# seamonster_smd_draft1.net
KiCad netlist of a schematic drawn in EAGLE
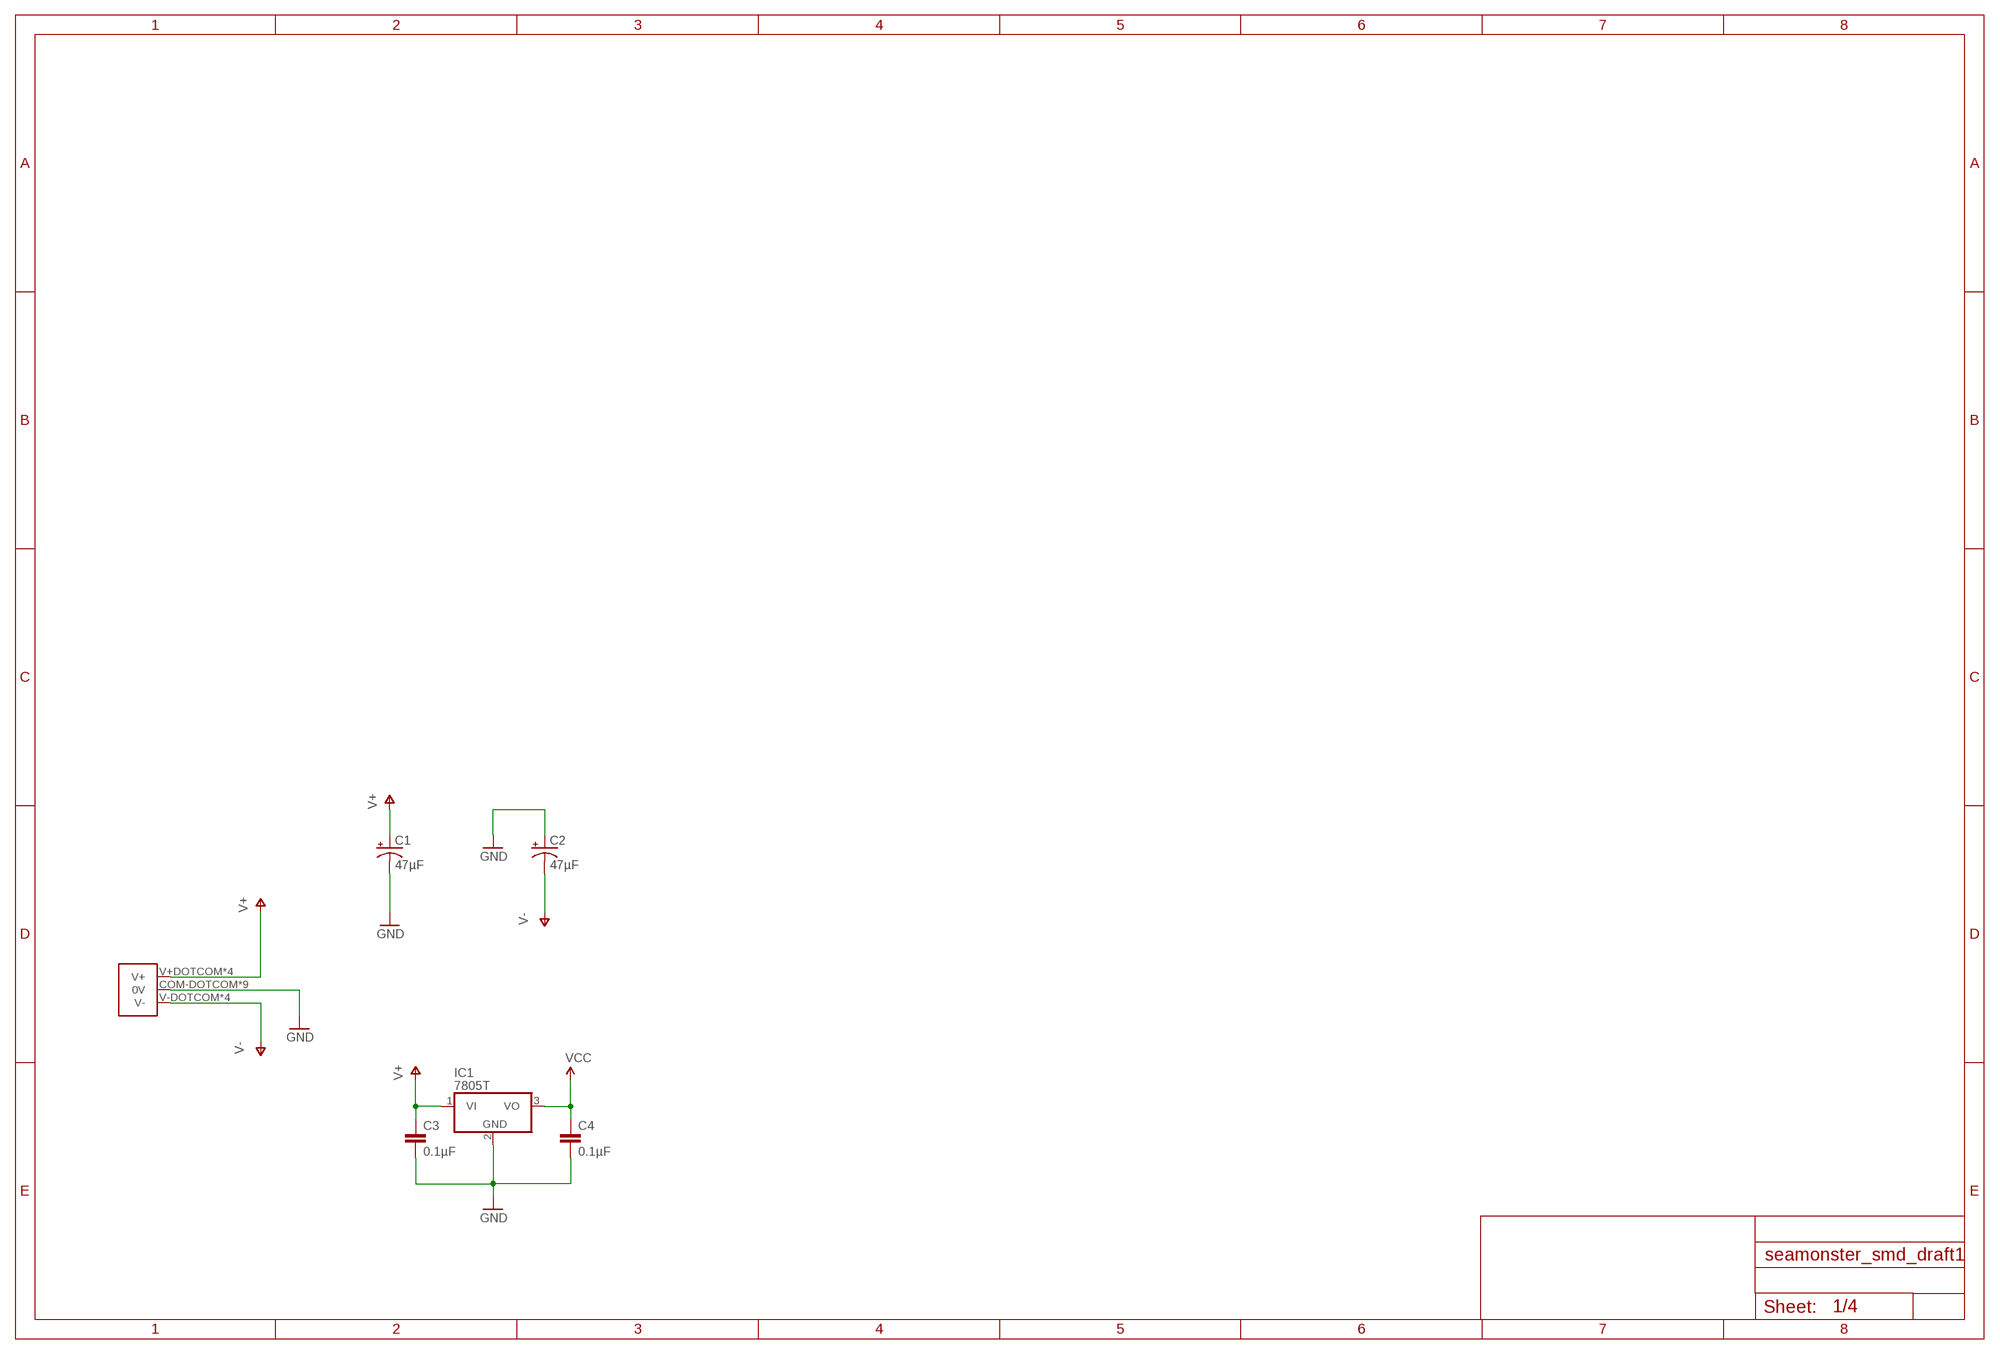
[diagram p0: schematic, sheet 1]
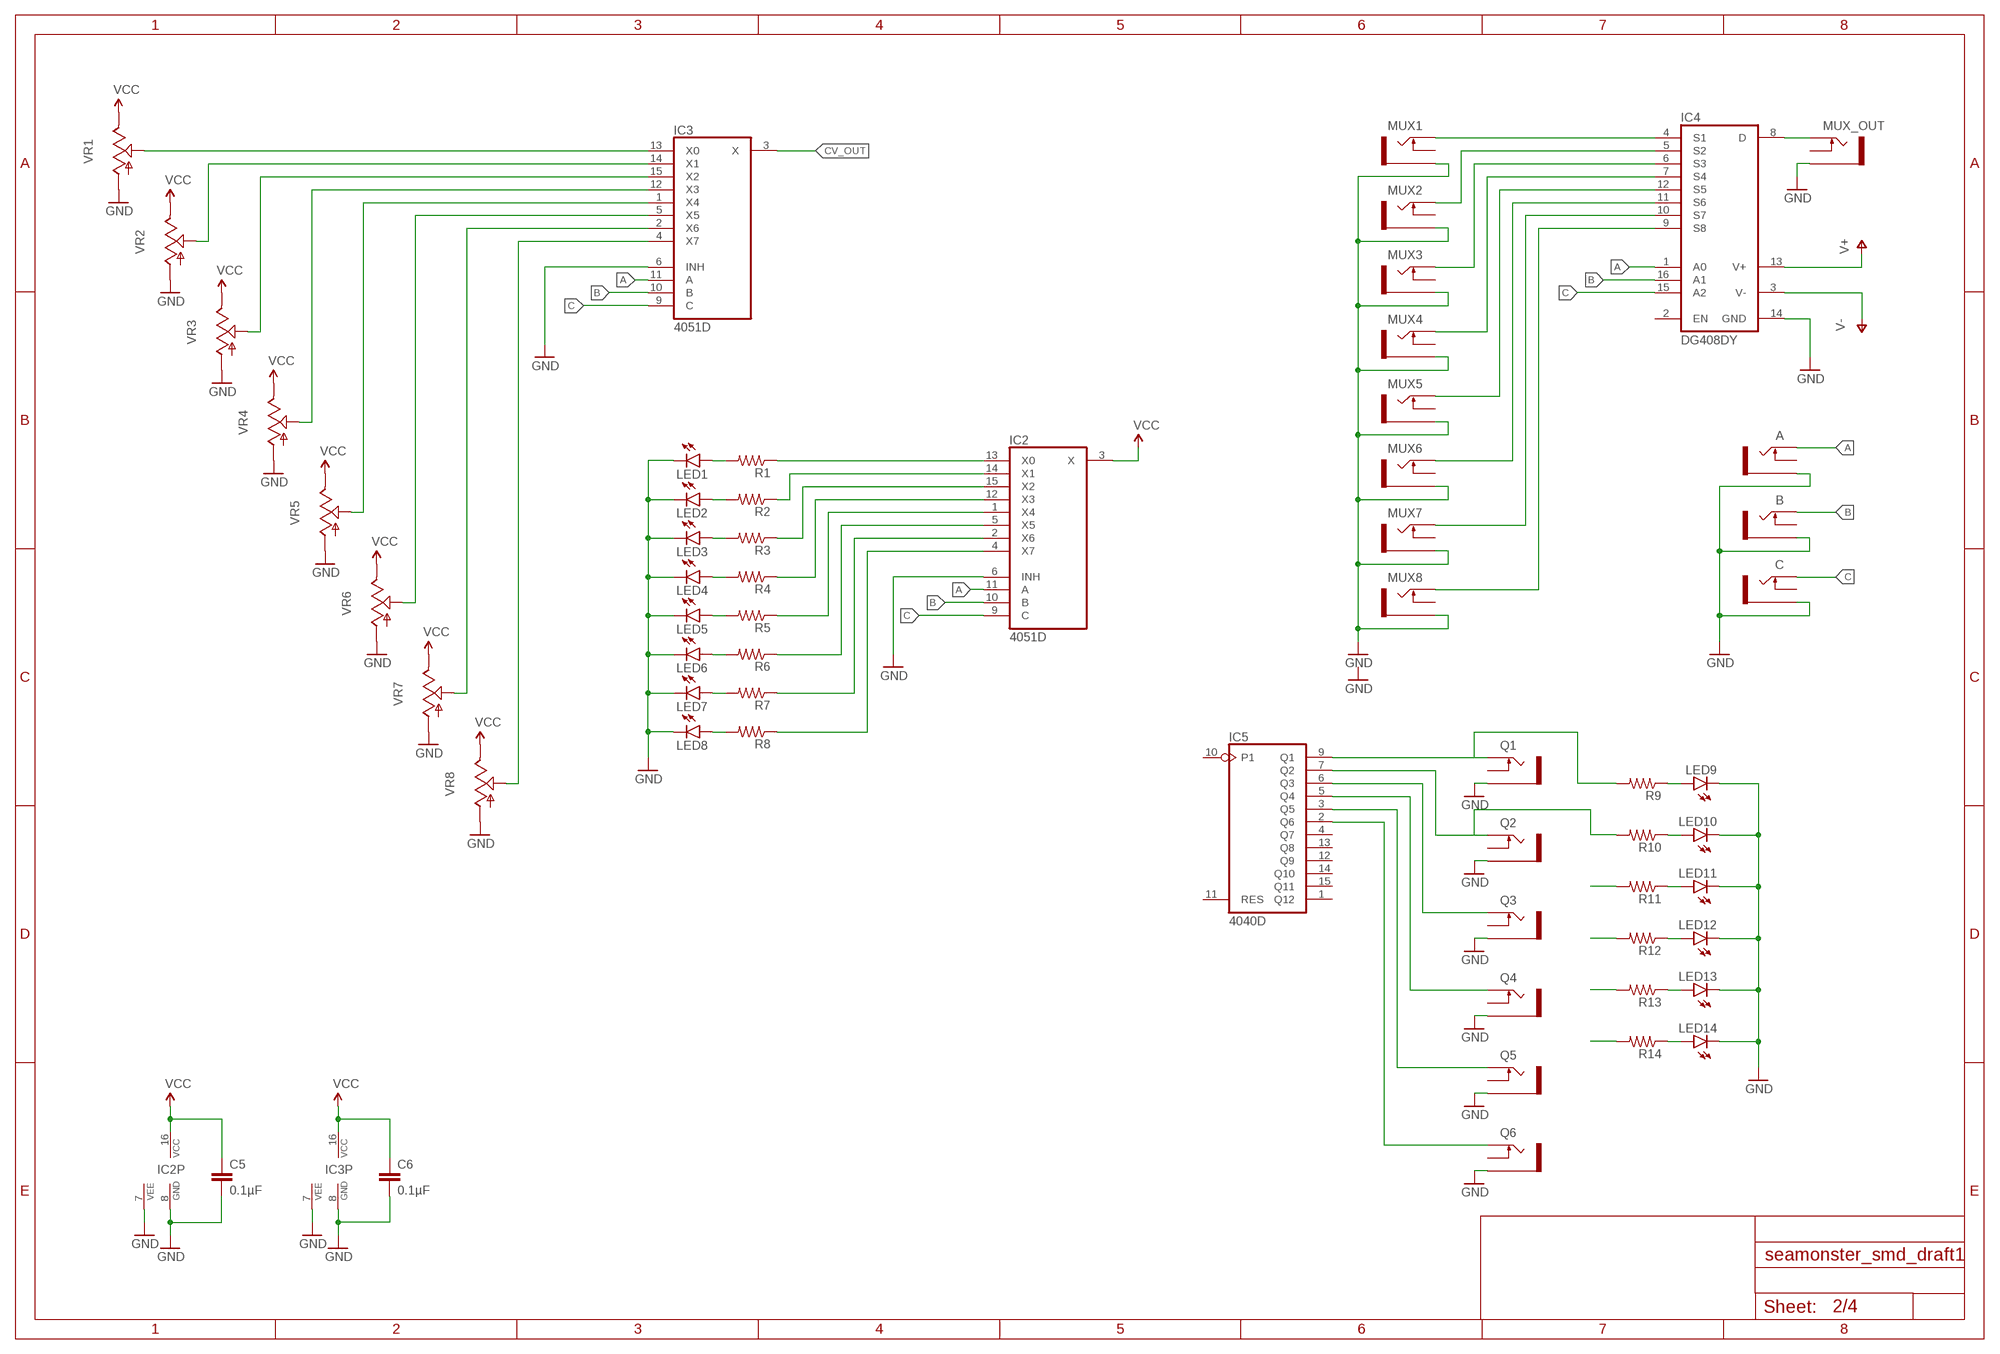
[diagram p1: schematic, sheet 2]
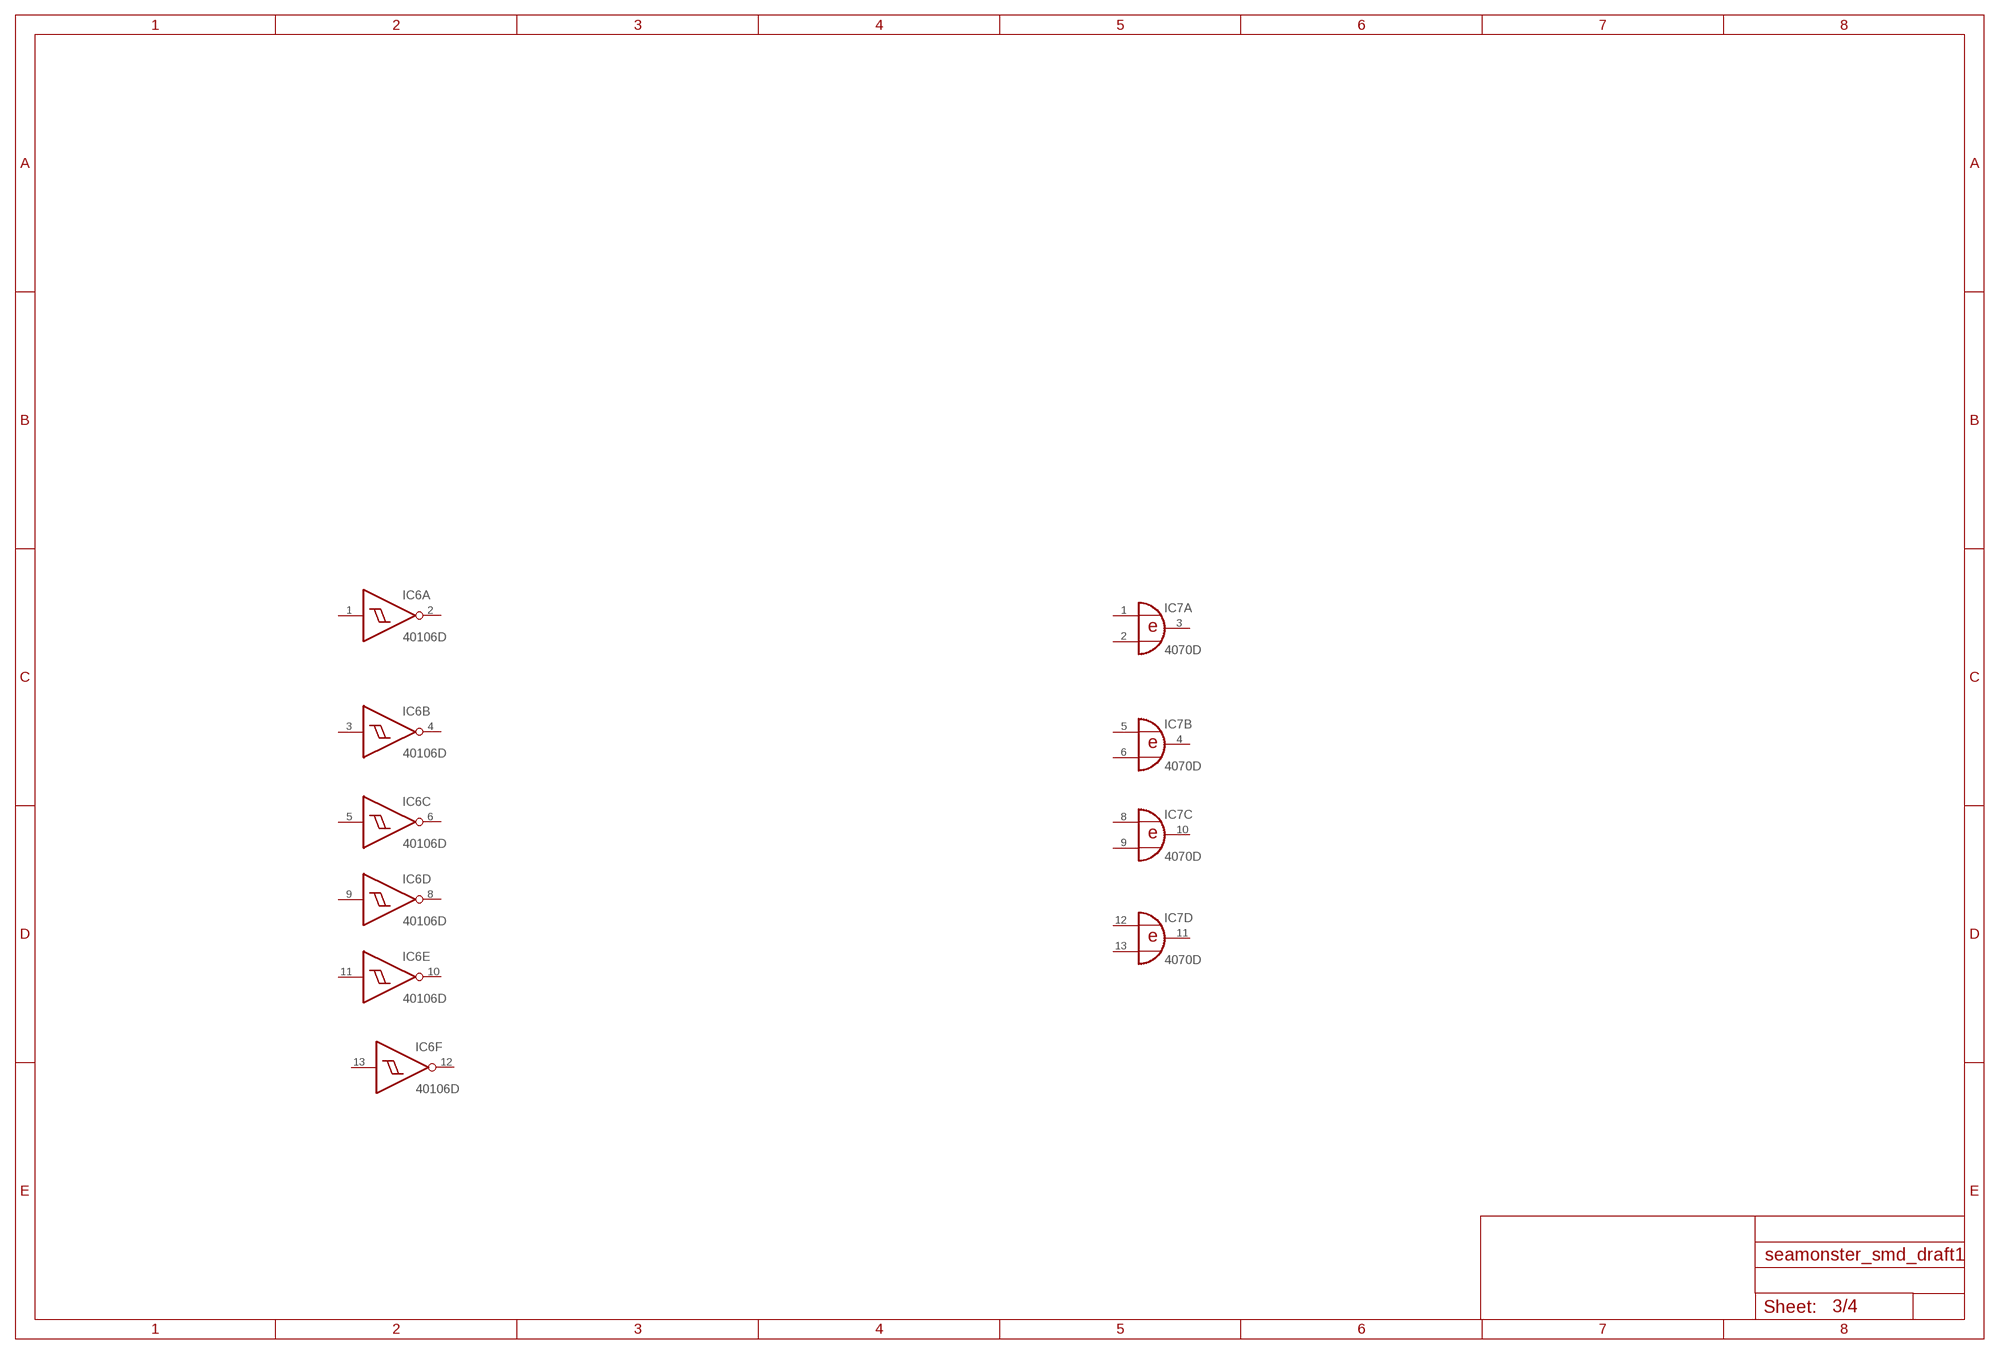
[diagram p2: schematic, sheet 3]
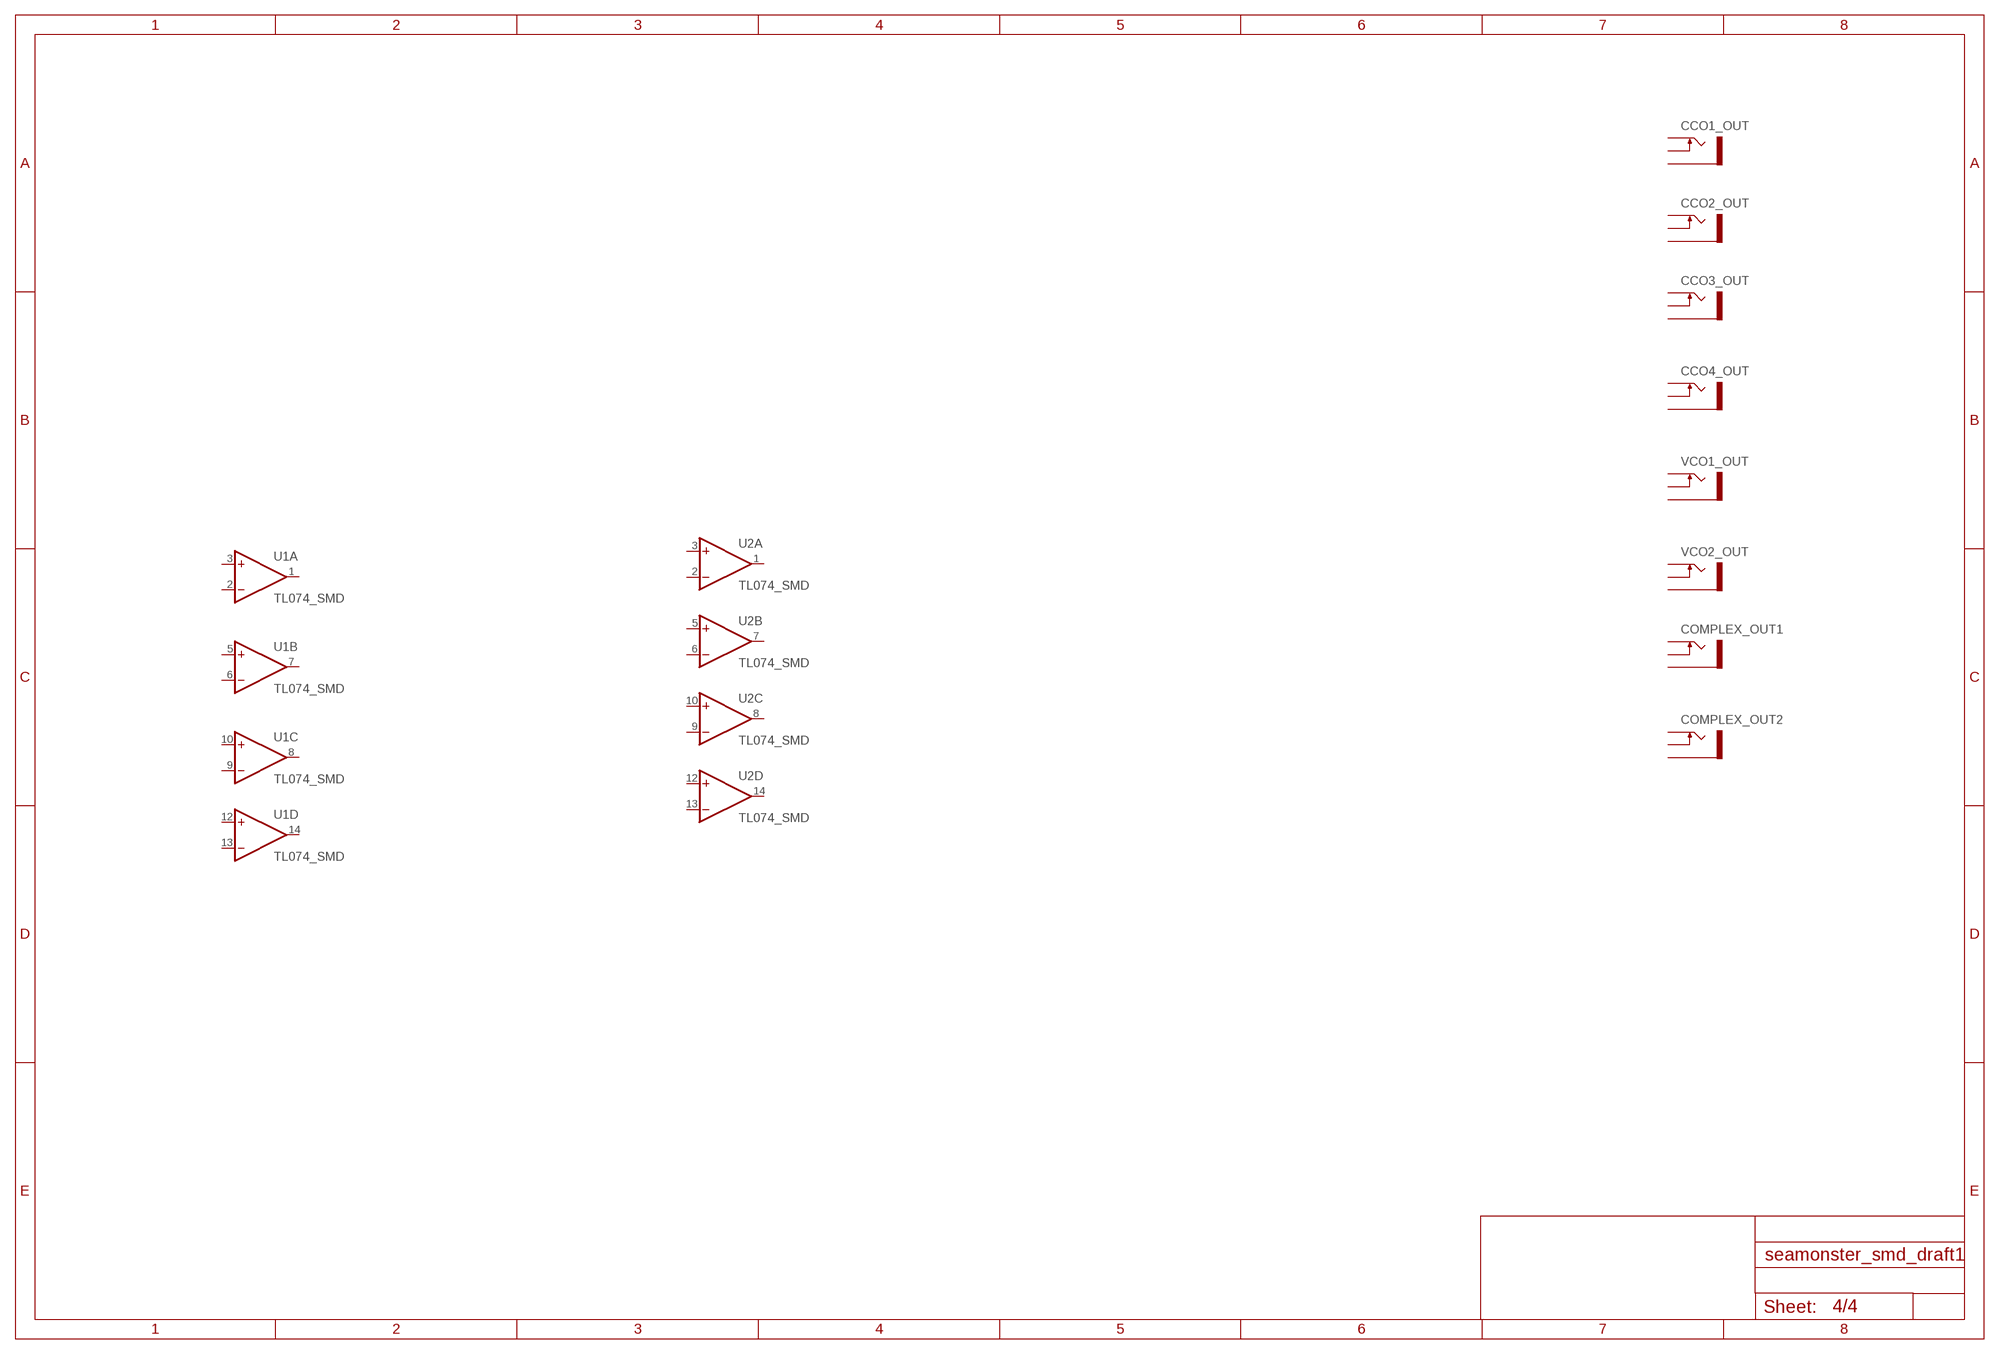
[diagram p3: schematic, sheet 4]

(export (version "E")
  (design (tool "Eeschema 10.0.6"))
  (components
    (comp (ref "IC6")
      (value "40106D")
      (footprint "eagle-import:SO14")
      (libsource (lib "eagle-import") (part "40106D"))
    )
    (comp (ref "IC7")
      (value "4070D")
      (footprint "eagle-import:SO14")
      (libsource (lib "eagle-import") (part "4070D"))
    )
    (comp (ref "CCO1_OUT")
      (value "THONKICONNNEW")
      (footprint "eagle-import:WQP-PJ301M-12_JACK")
      (libsource (lib "eagle-import") (part "THONKICONNNEW"))
    )
    (comp (ref "CCO2_OUT")
      (value "THONKICONNNEW")
      (footprint "eagle-import:WQP-PJ301M-12_JACK")
      (libsource (lib "eagle-import") (part "THONKICONNNEW"))
    )
    (comp (ref "CCO3_OUT")
      (value "THONKICONNNEW")
      (footprint "eagle-import:WQP-PJ301M-12_JACK")
      (libsource (lib "eagle-import") (part "THONKICONNNEW"))
    )
    (comp (ref "CCO4_OUT")
      (value "THONKICONNNEW")
      (footprint "eagle-import:WQP-PJ301M-12_JACK")
      (libsource (lib "eagle-import") (part "THONKICONNNEW"))
    )
    (comp (ref "COMPLEX_OUT1")
      (value "THONKICONNNEW")
      (footprint "eagle-import:WQP-PJ301M-12_JACK")
      (libsource (lib "eagle-import") (part "THONKICONNNEW"))
    )
    (comp (ref "COMPLEX_OUT2")
      (value "THONKICONNNEW")
      (footprint "eagle-import:WQP-PJ301M-12_JACK")
      (libsource (lib "eagle-import") (part "THONKICONNNEW"))
    )
    (comp (ref "U1")
      (value "TL074_SMD")
      (footprint "eagle-import:SO14")
      (libsource (lib "eagle-import") (part "TL074_SMD"))
    )
    (comp (ref "U2")
      (value "TL074_SMD")
      (footprint "eagle-import:SO14")
      (libsource (lib "eagle-import") (part "TL074_SMD"))
    )
    (comp (ref "VCO1_OUT")
      (value "THONKICONNNEW")
      (footprint "eagle-import:WQP-PJ301M-12_JACK")
      (libsource (lib "eagle-import") (part "THONKICONNNEW"))
    )
    (comp (ref "VCO2_OUT")
      (value "THONKICONNNEW")
      (footprint "eagle-import:WQP-PJ301M-12_JACK")
      (libsource (lib "eagle-import") (part "THONKICONNNEW"))
    )
    (comp (ref "A")
      (value "THONKICONNNEW")
      (footprint "eagle-import:WQP-PJ301M-12_JACK")
      (libsource (lib "eagle-import") (part "THONKICONNNEW"))
    )
    (comp (ref "B")
      (value "THONKICONNNEW")
      (footprint "eagle-import:WQP-PJ301M-12_JACK")
      (libsource (lib "eagle-import") (part "THONKICONNNEW"))
    )
    (comp (ref "C")
      (value "THONKICONNNEW")
      (footprint "eagle-import:WQP-PJ301M-12_JACK")
      (libsource (lib "eagle-import") (part "THONKICONNNEW"))
    )
    (comp (ref "C5")
      (value "0.1µF")
      (footprint "eagle-import:0805")
      (libsource (lib "eagle-import") (part "CAP0805"))
    )
    (comp (ref "C6")
      (value "0.1µF")
      (footprint "eagle-import:0805")
      (libsource (lib "eagle-import") (part "CAP0805"))
    )
    (comp (ref "IC2")
      (value "4051D")
      (footprint "eagle-import:SO16")
      (libsource (lib "eagle-import") (part "4051D"))
    )
    (comp (ref "IC3")
      (value "4051D")
      (footprint "eagle-import:SO16")
      (libsource (lib "eagle-import") (part "4051D"))
    )
    (comp (ref "IC4")
      (value "DG408DY")
      (footprint "eagle-import:SO16")
      (fields (field (name "MPN") "DG408DY+T"))
      (libsource (lib "eagle-import") (part "DG408DY"))
    )
    (comp (ref "IC5")
      (value "4040D")
      (footprint "eagle-import:SO16")
      (libsource (lib "eagle-import") (part "4040D"))
    )
    (comp (ref "LED1")
      (value "LED3MM")
      (footprint "eagle-import:LED3MM")
      (libsource (lib "eagle-import") (part "LED3MM"))
    )
    (comp (ref "LED2")
      (value "LED3MM")
      (footprint "eagle-import:LED3MM")
      (libsource (lib "eagle-import") (part "LED3MM"))
    )
    (comp (ref "LED3")
      (value "LED3MM")
      (footprint "eagle-import:LED3MM")
      (libsource (lib "eagle-import") (part "LED3MM"))
    )
    (comp (ref "LED4")
      (value "LED3MM")
      (footprint "eagle-import:LED3MM")
      (libsource (lib "eagle-import") (part "LED3MM"))
    )
    (comp (ref "LED5")
      (value "LED3MM")
      (footprint "eagle-import:LED3MM")
      (libsource (lib "eagle-import") (part "LED3MM"))
    )
    (comp (ref "LED6")
      (value "LED3MM")
      (footprint "eagle-import:LED3MM")
      (libsource (lib "eagle-import") (part "LED3MM"))
    )
    (comp (ref "LED7")
      (value "LED3MM")
      (footprint "eagle-import:LED3MM")
      (libsource (lib "eagle-import") (part "LED3MM"))
    )
    (comp (ref "LED8")
      (value "LED3MM")
      (footprint "eagle-import:LED3MM")
      (libsource (lib "eagle-import") (part "LED3MM"))
    )
    (comp (ref "LED9")
      (value "LED3MM")
      (footprint "eagle-import:LED3MM")
      (libsource (lib "eagle-import") (part "LED3MM"))
    )
    (comp (ref "LED10")
      (value "LED3MM")
      (footprint "eagle-import:LED3MM")
      (libsource (lib "eagle-import") (part "LED3MM"))
    )
    (comp (ref "LED11")
      (value "LED3MM")
      (footprint "eagle-import:LED3MM")
      (libsource (lib "eagle-import") (part "LED3MM"))
    )
    (comp (ref "LED12")
      (value "LED3MM")
      (footprint "eagle-import:LED3MM")
      (libsource (lib "eagle-import") (part "LED3MM"))
    )
    (comp (ref "LED13")
      (value "LED3MM")
      (footprint "eagle-import:LED3MM")
      (libsource (lib "eagle-import") (part "LED3MM"))
    )
    (comp (ref "LED14")
      (value "LED3MM")
      (footprint "eagle-import:LED3MM")
      (libsource (lib "eagle-import") (part "LED3MM"))
    )
    (comp (ref "MUX1")
      (value "THONKICONNNEW")
      (footprint "eagle-import:WQP-PJ301M-12_JACK")
      (libsource (lib "eagle-import") (part "THONKICONNNEW"))
    )
    (comp (ref "MUX2")
      (value "THONKICONNNEW")
      (footprint "eagle-import:WQP-PJ301M-12_JACK")
      (libsource (lib "eagle-import") (part "THONKICONNNEW"))
    )
    (comp (ref "MUX3")
      (value "THONKICONNNEW")
      (footprint "eagle-import:WQP-PJ301M-12_JACK")
      (libsource (lib "eagle-import") (part "THONKICONNNEW"))
    )
    (comp (ref "MUX4")
      (value "THONKICONNNEW")
      (footprint "eagle-import:WQP-PJ301M-12_JACK")
      (libsource (lib "eagle-import") (part "THONKICONNNEW"))
    )
    (comp (ref "MUX5")
      (value "THONKICONNNEW")
      (footprint "eagle-import:WQP-PJ301M-12_JACK")
      (libsource (lib "eagle-import") (part "THONKICONNNEW"))
    )
    (comp (ref "MUX6")
      (value "THONKICONNNEW")
      (footprint "eagle-import:WQP-PJ301M-12_JACK")
      (libsource (lib "eagle-import") (part "THONKICONNNEW"))
    )
    (comp (ref "MUX7")
      (value "THONKICONNNEW")
      (footprint "eagle-import:WQP-PJ301M-12_JACK")
      (libsource (lib "eagle-import") (part "THONKICONNNEW"))
    )
    (comp (ref "MUX8")
      (value "THONKICONNNEW")
      (footprint "eagle-import:WQP-PJ301M-12_JACK")
      (libsource (lib "eagle-import") (part "THONKICONNNEW"))
    )
    (comp (ref "MUX_OUT")
      (value "THONKICONNNEW")
      (footprint "eagle-import:WQP-PJ301M-12_JACK")
      (libsource (lib "eagle-import") (part "THONKICONNNEW"))
    )
    (comp (ref "Q1")
      (value "THONKICONNNEW")
      (footprint "eagle-import:WQP-PJ301M-12_JACK")
      (libsource (lib "eagle-import") (part "THONKICONNNEW"))
    )
    (comp (ref "Q2")
      (value "THONKICONNNEW")
      (footprint "eagle-import:WQP-PJ301M-12_JACK")
      (libsource (lib "eagle-import") (part "THONKICONNNEW"))
    )
    (comp (ref "Q3")
      (value "THONKICONNNEW")
      (footprint "eagle-import:WQP-PJ301M-12_JACK")
      (libsource (lib "eagle-import") (part "THONKICONNNEW"))
    )
    (comp (ref "Q4")
      (value "THONKICONNNEW")
      (footprint "eagle-import:WQP-PJ301M-12_JACK")
      (libsource (lib "eagle-import") (part "THONKICONNNEW"))
    )
    (comp (ref "Q5")
      (value "THONKICONNNEW")
      (footprint "eagle-import:WQP-PJ301M-12_JACK")
      (libsource (lib "eagle-import") (part "THONKICONNNEW"))
    )
    (comp (ref "Q6")
      (value "THONKICONNNEW")
      (footprint "eagle-import:WQP-PJ301M-12_JACK")
      (libsource (lib "eagle-import") (part "THONKICONNNEW"))
    )
    (comp (ref "R1")
      (value "RESISTOR0805-RES")
      (footprint "eagle-import:0805")
      (libsource (lib "eagle-import") (part "RESISTOR0805-RES"))
    )
    (comp (ref "R2")
      (value "RESISTOR0805-RES")
      (footprint "eagle-import:0805")
      (libsource (lib "eagle-import") (part "RESISTOR0805-RES"))
    )
    (comp (ref "R3")
      (value "RESISTOR0805-RES")
      (footprint "eagle-import:0805")
      (libsource (lib "eagle-import") (part "RESISTOR0805-RES"))
    )
    (comp (ref "R4")
      (value "RESISTOR0805-RES")
      (footprint "eagle-import:0805")
      (libsource (lib "eagle-import") (part "RESISTOR0805-RES"))
    )
    (comp (ref "R5")
      (value "RESISTOR0805-RES")
      (footprint "eagle-import:0805")
      (libsource (lib "eagle-import") (part "RESISTOR0805-RES"))
    )
    (comp (ref "R6")
      (value "RESISTOR0805-RES")
      (footprint "eagle-import:0805")
      (libsource (lib "eagle-import") (part "RESISTOR0805-RES"))
    )
    (comp (ref "R7")
      (value "RESISTOR0805-RES")
      (footprint "eagle-import:0805")
      (libsource (lib "eagle-import") (part "RESISTOR0805-RES"))
    )
    (comp (ref "R8")
      (value "RESISTOR0805-RES")
      (footprint "eagle-import:0805")
      (libsource (lib "eagle-import") (part "RESISTOR0805-RES"))
    )
    (comp (ref "R9")
      (value "RESISTOR0805-RES")
      (footprint "eagle-import:0805")
      (libsource (lib "eagle-import") (part "RESISTOR0805-RES"))
    )
    (comp (ref "R10")
      (value "RESISTOR0805-RES")
      (footprint "eagle-import:0805")
      (libsource (lib "eagle-import") (part "RESISTOR0805-RES"))
    )
    (comp (ref "R11")
      (value "RESISTOR0805-RES")
      (footprint "eagle-import:0805")
      (libsource (lib "eagle-import") (part "RESISTOR0805-RES"))
    )
    (comp (ref "R12")
      (value "RESISTOR0805-RES")
      (footprint "eagle-import:0805")
      (libsource (lib "eagle-import") (part "RESISTOR0805-RES"))
    )
    (comp (ref "R13")
      (value "RESISTOR0805-RES")
      (footprint "eagle-import:0805")
      (libsource (lib "eagle-import") (part "RESISTOR0805-RES"))
    )
    (comp (ref "R14")
      (value "RESISTOR0805-RES")
      (footprint "eagle-import:0805")
      (libsource (lib "eagle-import") (part "RESISTOR0805-RES"))
    )
    (comp (ref "VR1")
      (value "9MM_SNAP-IN_POT_")
      (footprint "eagle-import:9MM_SNAP-IN_POT")
      (libsource (lib "eagle-import") (part "9MM_SNAP-IN_POT_"))
    )
    (comp (ref "VR2")
      (value "9MM_SNAP-IN_POT_")
      (footprint "eagle-import:9MM_SNAP-IN_POT")
      (libsource (lib "eagle-import") (part "9MM_SNAP-IN_POT_"))
    )
    (comp (ref "VR3")
      (value "9MM_SNAP-IN_POT_")
      (footprint "eagle-import:9MM_SNAP-IN_POT")
      (libsource (lib "eagle-import") (part "9MM_SNAP-IN_POT_"))
    )
    (comp (ref "VR4")
      (value "9MM_SNAP-IN_POT_")
      (footprint "eagle-import:9MM_SNAP-IN_POT")
      (libsource (lib "eagle-import") (part "9MM_SNAP-IN_POT_"))
    )
    (comp (ref "VR5")
      (value "9MM_SNAP-IN_POT_")
      (footprint "eagle-import:9MM_SNAP-IN_POT")
      (libsource (lib "eagle-import") (part "9MM_SNAP-IN_POT_"))
    )
    (comp (ref "VR6")
      (value "9MM_SNAP-IN_POT_")
      (footprint "eagle-import:9MM_SNAP-IN_POT")
      (libsource (lib "eagle-import") (part "9MM_SNAP-IN_POT_"))
    )
    (comp (ref "VR7")
      (value "9MM_SNAP-IN_POT_")
      (footprint "eagle-import:9MM_SNAP-IN_POT")
      (libsource (lib "eagle-import") (part "9MM_SNAP-IN_POT_"))
    )
    (comp (ref "VR8")
      (value "9MM_SNAP-IN_POT_")
      (footprint "eagle-import:9MM_SNAP-IN_POT")
      (libsource (lib "eagle-import") (part "9MM_SNAP-IN_POT_"))
    )
    (comp (ref "C1")
      (value "47µF")
      (footprint "eagle-import:CPOL-RADIAL-10UF-25V")
      (libsource (lib "eagle-import") (part "CAP_POLPTH2"))
    )
    (comp (ref "C2")
      (value "47µF")
      (footprint "eagle-import:CPOL-RADIAL-10UF-25V")
      (libsource (lib "eagle-import") (part "CAP_POLPTH2"))
    )
    (comp (ref "C3")
      (value "0.1µF")
      (footprint "eagle-import:0805")
      (libsource (lib "eagle-import") (part "CAP0805"))
    )
    (comp (ref "C4")
      (value "0.1µF")
      (footprint "eagle-import:0805")
      (libsource (lib "eagle-import") (part "CAP0805"))
    )
    (comp (ref "IC1")
      (value "7805T")
      (footprint "eagle-import:TO220H")
      (libsource (lib "eagle-import") (part "78T05"))
    )
    (comp (ref "U$1")
      (value "COMBO_POWER")
      (footprint "eagle-import:COMBO_POWER")
      (libsource (lib "eagle-import") (part "COMBO_POWER"))
    )
  )
  (nets
    (net (code "1") (name "A") (class "Default")
      (node (ref "A") (pin "P$1_TIP") (pinfunction "TIP_P$1_TIP") (pintype "passive"))
      (node (ref "IC2") (pin "11") (pinfunction "A_11") (pintype "input"))
      (node (ref "IC3") (pin "11") (pinfunction "A_11") (pintype "input"))
      (node (ref "IC4") (pin "1") (pinfunction "A0_1") (pintype "input"))
    )
    (net (code "2") (name "B") (class "Default")
      (node (ref "B") (pin "P$1_TIP") (pinfunction "TIP_P$1_TIP") (pintype "passive"))
      (node (ref "IC2") (pin "10") (pinfunction "B_10") (pintype "input"))
      (node (ref "IC3") (pin "10") (pinfunction "B_10") (pintype "input"))
      (node (ref "IC4") (pin "16") (pinfunction "A1_16") (pintype "input"))
    )
    (net (code "3") (name "C") (class "Default")
      (node (ref "C") (pin "P$1_TIP") (pinfunction "TIP_P$1_TIP") (pintype "passive"))
      (node (ref "IC2") (pin "9") (pinfunction "C_9") (pintype "input"))
      (node (ref "IC3") (pin "9") (pinfunction "C_9") (pintype "input"))
      (node (ref "IC4") (pin "15") (pinfunction "A2_15") (pintype "input"))
    )
    (net (code "4") (name "CV_OUT") (class "Default")
      (node (ref "IC3") (pin "3") (pinfunction "X_3") (pintype "bidirectional"))
    )
    (net (code "5") (name "GND") (class "Default")
      (node (ref "A") (pin "P$3_SLEEVE") (pinfunction "SLEEVE_P$3_SLEEVE") (pintype "passive"))
      (node (ref "B") (pin "P$3_SLEEVE") (pinfunction "SLEEVE_P$3_SLEEVE") (pintype "passive"))
      (node (ref "C") (pin "P$3_SLEEVE") (pinfunction "SLEEVE_P$3_SLEEVE") (pintype "passive"))
      (node (ref "C1") (pin "2") (pinfunction "-_2") (pintype "passive"))
      (node (ref "C2") (pin "1") (pinfunction "+_1") (pintype "passive"))
      (node (ref "C3") (pin "2") (pinfunction "2_2") (pintype "passive"))
      (node (ref "C4") (pin "2") (pinfunction "2_2") (pintype "passive"))
      (node (ref "C5") (pin "2") (pinfunction "2_2") (pintype "passive"))
      (node (ref "C6") (pin "2") (pinfunction "2_2") (pintype "passive"))
      (node (ref "IC1") (pin "2") (pinfunction "GND_2") (pintype "passive"))
      (node (ref "IC2") (pin "6") (pinfunction "INH_6") (pintype "input"))
      (node (ref "IC2") (pin "7") (pinfunction "VEE_7") (pintype "power_in"))
      (node (ref "IC2") (pin "8") (pinfunction "GND_8") (pintype "power_in"))
      (node (ref "IC3") (pin "6") (pinfunction "INH_6") (pintype "input"))
      (node (ref "IC3") (pin "7") (pinfunction "VEE_7") (pintype "power_in"))
      (node (ref "IC3") (pin "8") (pinfunction "GND_8") (pintype "power_in"))
      (node (ref "IC4") (pin "14") (pinfunction "GND_14") (pintype "power_in"))
      (node (ref "LED1") (pin "K") (pinfunction "C_K") (pintype "passive"))
      (node (ref "LED10") (pin "K") (pinfunction "C_K") (pintype "passive"))
      (node (ref "LED11") (pin "K") (pinfunction "C_K") (pintype "passive"))
      (node (ref "LED12") (pin "K") (pinfunction "C_K") (pintype "passive"))
      (node (ref "LED13") (pin "K") (pinfunction "C_K") (pintype "passive"))
      (node (ref "LED14") (pin "K") (pinfunction "C_K") (pintype "passive"))
      (node (ref "LED2") (pin "K") (pinfunction "C_K") (pintype "passive"))
      (node (ref "LED3") (pin "K") (pinfunction "C_K") (pintype "passive"))
      (node (ref "LED4") (pin "K") (pinfunction "C_K") (pintype "passive"))
      (node (ref "LED5") (pin "K") (pinfunction "C_K") (pintype "passive"))
      (node (ref "LED6") (pin "K") (pinfunction "C_K") (pintype "passive"))
      (node (ref "LED7") (pin "K") (pinfunction "C_K") (pintype "passive"))
      (node (ref "LED8") (pin "K") (pinfunction "C_K") (pintype "passive"))
      (node (ref "LED9") (pin "K") (pinfunction "C_K") (pintype "passive"))
      (node (ref "MUX1") (pin "P$3_SLEEVE") (pinfunction "SLEEVE_P$3_SLEEVE") (pintype "passive"))
      (node (ref "MUX2") (pin "P$3_SLEEVE") (pinfunction "SLEEVE_P$3_SLEEVE") (pintype "passive"))
      (node (ref "MUX3") (pin "P$3_SLEEVE") (pinfunction "SLEEVE_P$3_SLEEVE") (pintype "passive"))
      (node (ref "MUX4") (pin "P$3_SLEEVE") (pinfunction "SLEEVE_P$3_SLEEVE") (pintype "passive"))
      (node (ref "MUX5") (pin "P$3_SLEEVE") (pinfunction "SLEEVE_P$3_SLEEVE") (pintype "passive"))
      (node (ref "MUX6") (pin "P$3_SLEEVE") (pinfunction "SLEEVE_P$3_SLEEVE") (pintype "passive"))
      (node (ref "MUX7") (pin "P$3_SLEEVE") (pinfunction "SLEEVE_P$3_SLEEVE") (pintype "passive"))
      (node (ref "MUX8") (pin "P$3_SLEEVE") (pinfunction "SLEEVE_P$3_SLEEVE") (pintype "passive"))
      (node (ref "MUX_OUT") (pin "P$3_SLEEVE") (pinfunction "SLEEVE_P$3_SLEEVE") (pintype "passive"))
      (node (ref "Q1") (pin "P$3_SLEEVE") (pinfunction "SLEEVE_P$3_SLEEVE") (pintype "passive"))
      (node (ref "Q2") (pin "P$3_SLEEVE") (pinfunction "SLEEVE_P$3_SLEEVE") (pintype "passive"))
      (node (ref "Q3") (pin "P$3_SLEEVE") (pinfunction "SLEEVE_P$3_SLEEVE") (pintype "passive"))
      (node (ref "Q4") (pin "P$3_SLEEVE") (pinfunction "SLEEVE_P$3_SLEEVE") (pintype "passive"))
      (node (ref "Q5") (pin "P$3_SLEEVE") (pinfunction "SLEEVE_P$3_SLEEVE") (pintype "passive"))
      (node (ref "Q6") (pin "P$3_SLEEVE") (pinfunction "SLEEVE_P$3_SLEEVE") (pintype "passive"))
      (node (ref "U$1") (pin "COM-DOTCOM") (pinfunction "0V_COM-DOTCOM") (pintype "bidirectional"))
      (node (ref "U$1") (pin "COM-EURO1") (pinfunction "0V_COM-EURO1") (pintype "bidirectional"))
      (node (ref "U$1") (pin "COM-EURO2") (pinfunction "0V_COM-EURO2") (pintype "bidirectional"))
      (node (ref "U$1") (pin "COM-EURO3") (pinfunction "0V_COM-EURO3") (pintype "bidirectional"))
      (node (ref "U$1") (pin "COM-EURO4") (pinfunction "0V_COM-EURO4") (pintype "bidirectional"))
      (node (ref "U$1") (pin "COM-EURO5") (pinfunction "0V_COM-EURO5") (pintype "bidirectional"))
      (node (ref "U$1") (pin "COM-EURO6") (pinfunction "0V_COM-EURO6") (pintype "bidirectional"))
      (node (ref "U$1") (pin "COM-MOTM1") (pinfunction "0V_COM-MOTM1") (pintype "bidirectional"))
      (node (ref "U$1") (pin "COM_MOTM2") (pinfunction "0V_COM_MOTM2") (pintype "bidirectional"))
      (node (ref "VR1") (pin "1") (pinfunction "A_1") (pintype "passive"))
      (node (ref "VR2") (pin "1") (pinfunction "A_1") (pintype "passive"))
      (node (ref "VR3") (pin "1") (pinfunction "A_1") (pintype "passive"))
      (node (ref "VR4") (pin "1") (pinfunction "A_1") (pintype "passive"))
      (node (ref "VR5") (pin "1") (pinfunction "A_1") (pintype "passive"))
      (node (ref "VR6") (pin "1") (pinfunction "A_1") (pintype "passive"))
      (node (ref "VR7") (pin "1") (pinfunction "A_1") (pintype "passive"))
      (node (ref "VR8") (pin "1") (pinfunction "A_1") (pintype "passive"))
    )
    (net (code "6") (name "Net-(IC2A-X0)") (class "Default")
      (node (ref "IC2") (pin "13") (pinfunction "X0_13") (pintype "bidirectional"))
      (node (ref "R1") (pin "1") (pinfunction "1_1") (pintype "passive"))
    )
    (net (code "7") (name "Net-(IC2A-X1)") (class "Default")
      (node (ref "IC2") (pin "14") (pinfunction "X1_14") (pintype "bidirectional"))
      (node (ref "R2") (pin "1") (pinfunction "1_1") (pintype "passive"))
    )
    (net (code "8") (name "Net-(IC2A-X2)") (class "Default")
      (node (ref "IC2") (pin "15") (pinfunction "X2_15") (pintype "bidirectional"))
      (node (ref "R3") (pin "1") (pinfunction "1_1") (pintype "passive"))
    )
    (net (code "9") (name "Net-(IC2A-X3)") (class "Default")
      (node (ref "IC2") (pin "12") (pinfunction "X3_12") (pintype "bidirectional"))
      (node (ref "R4") (pin "1") (pinfunction "1_1") (pintype "passive"))
    )
    (net (code "10") (name "Net-(IC2A-X4)") (class "Default")
      (node (ref "IC2") (pin "1") (pinfunction "X4_1") (pintype "bidirectional"))
      (node (ref "R5") (pin "1") (pinfunction "1_1") (pintype "passive"))
    )
    (net (code "11") (name "Net-(IC2A-X5)") (class "Default")
      (node (ref "IC2") (pin "5") (pinfunction "X5_5") (pintype "bidirectional"))
      (node (ref "R6") (pin "1") (pinfunction "1_1") (pintype "passive"))
    )
    (net (code "12") (name "Net-(IC2A-X6)") (class "Default")
      (node (ref "IC2") (pin "2") (pinfunction "X6_2") (pintype "bidirectional"))
      (node (ref "R7") (pin "1") (pinfunction "1_1") (pintype "passive"))
    )
    (net (code "13") (name "Net-(IC2A-X7)") (class "Default")
      (node (ref "IC2") (pin "4") (pinfunction "X7_4") (pintype "bidirectional"))
      (node (ref "R8") (pin "1") (pinfunction "1_1") (pintype "passive"))
    )
    (net (code "14") (name "Net-(IC3A-X0)") (class "Default")
      (node (ref "IC3") (pin "13") (pinfunction "X0_13") (pintype "bidirectional"))
      (node (ref "VR1") (pin "2") (pinfunction "S_2") (pintype "passive"))
    )
    (net (code "15") (name "Net-(IC3A-X1)") (class "Default")
      (node (ref "IC3") (pin "14") (pinfunction "X1_14") (pintype "bidirectional"))
      (node (ref "VR2") (pin "2") (pinfunction "S_2") (pintype "passive"))
    )
    (net (code "16") (name "Net-(IC3A-X2)") (class "Default")
      (node (ref "IC3") (pin "15") (pinfunction "X2_15") (pintype "bidirectional"))
      (node (ref "VR3") (pin "2") (pinfunction "S_2") (pintype "passive"))
    )
    (net (code "17") (name "Net-(IC3A-X3)") (class "Default")
      (node (ref "IC3") (pin "12") (pinfunction "X3_12") (pintype "bidirectional"))
      (node (ref "VR4") (pin "2") (pinfunction "S_2") (pintype "passive"))
    )
    (net (code "18") (name "Net-(IC3A-X4)") (class "Default")
      (node (ref "IC3") (pin "1") (pinfunction "X4_1") (pintype "bidirectional"))
      (node (ref "VR5") (pin "2") (pinfunction "S_2") (pintype "passive"))
    )
    (net (code "19") (name "Net-(IC3A-X5)") (class "Default")
      (node (ref "IC3") (pin "5") (pinfunction "X5_5") (pintype "bidirectional"))
      (node (ref "VR6") (pin "2") (pinfunction "S_2") (pintype "passive"))
    )
    (net (code "20") (name "Net-(IC3A-X6)") (class "Default")
      (node (ref "IC3") (pin "2") (pinfunction "X6_2") (pintype "bidirectional"))
      (node (ref "VR7") (pin "2") (pinfunction "S_2") (pintype "passive"))
    )
    (net (code "21") (name "Net-(IC3A-X7)") (class "Default")
      (node (ref "IC3") (pin "4") (pinfunction "X7_4") (pintype "bidirectional"))
      (node (ref "VR8") (pin "2") (pinfunction "S_2") (pintype "passive"))
    )
    (net (code "22") (name "Net-(IC4-D)") (class "Default")
      (node (ref "IC4") (pin "8") (pinfunction "D_8") (pintype "passive"))
      (node (ref "MUX_OUT") (pin "P$1_TIP") (pinfunction "TIP_P$1_TIP") (pintype "passive"))
    )
    (net (code "23") (name "Net-(IC4-S1)") (class "Default")
      (node (ref "IC4") (pin "4") (pinfunction "S1_4") (pintype "passive"))
      (node (ref "MUX1") (pin "P$1_TIP") (pinfunction "TIP_P$1_TIP") (pintype "passive"))
    )
    (net (code "24") (name "Net-(IC4-S2)") (class "Default")
      (node (ref "IC4") (pin "5") (pinfunction "S2_5") (pintype "passive"))
      (node (ref "MUX2") (pin "P$1_TIP") (pinfunction "TIP_P$1_TIP") (pintype "passive"))
    )
    (net (code "25") (name "Net-(IC4-S3)") (class "Default")
      (node (ref "IC4") (pin "6") (pinfunction "S3_6") (pintype "passive"))
      (node (ref "MUX3") (pin "P$1_TIP") (pinfunction "TIP_P$1_TIP") (pintype "passive"))
    )
    (net (code "26") (name "Net-(IC4-S4)") (class "Default")
      (node (ref "IC4") (pin "7") (pinfunction "S4_7") (pintype "passive"))
      (node (ref "MUX4") (pin "P$1_TIP") (pinfunction "TIP_P$1_TIP") (pintype "passive"))
    )
    (net (code "27") (name "Net-(IC4-S5)") (class "Default")
      (node (ref "IC4") (pin "12") (pinfunction "S5_12") (pintype "passive"))
      (node (ref "MUX5") (pin "P$1_TIP") (pinfunction "TIP_P$1_TIP") (pintype "passive"))
    )
    (net (code "28") (name "Net-(IC4-S6)") (class "Default")
      (node (ref "IC4") (pin "11") (pinfunction "S6_11") (pintype "passive"))
      (node (ref "MUX6") (pin "P$1_TIP") (pinfunction "TIP_P$1_TIP") (pintype "passive"))
    )
    (net (code "29") (name "Net-(IC4-S7)") (class "Default")
      (node (ref "IC4") (pin "10") (pinfunction "S7_10") (pintype "passive"))
      (node (ref "MUX7") (pin "P$1_TIP") (pinfunction "TIP_P$1_TIP") (pintype "passive"))
    )
    (net (code "30") (name "Net-(IC4-S8)") (class "Default")
      (node (ref "IC4") (pin "9") (pinfunction "S8_9") (pintype "passive"))
      (node (ref "MUX8") (pin "P$1_TIP") (pinfunction "TIP_P$1_TIP") (pintype "passive"))
    )
    (net (code "31") (name "Net-(IC5A-Q1)") (class "Default")
      (node (ref "IC5") (pin "9") (pinfunction "Q1_9") (pintype "output"))
      (node (ref "Q1") (pin "P$1_TIP") (pinfunction "TIP_P$1_TIP") (pintype "passive"))
      (node (ref "R9") (pin "2") (pinfunction "2_2") (pintype "passive"))
    )
    (net (code "32") (name "Net-(IC5A-Q2)") (class "Default")
      (node (ref "IC5") (pin "7") (pinfunction "Q2_7") (pintype "output"))
      (node (ref "Q2") (pin "P$1_TIP") (pinfunction "TIP_P$1_TIP") (pintype "passive"))
      (node (ref "R10") (pin "2") (pinfunction "2_2") (pintype "passive"))
    )
    (net (code "33") (name "Net-(IC5A-Q3)") (class "Default")
      (node (ref "IC5") (pin "6") (pinfunction "Q3_6") (pintype "output"))
      (node (ref "Q3") (pin "P$1_TIP") (pinfunction "TIP_P$1_TIP") (pintype "passive"))
    )
    (net (code "34") (name "Net-(IC5A-Q4)") (class "Default")
      (node (ref "IC5") (pin "5") (pinfunction "Q4_5") (pintype "output"))
      (node (ref "Q4") (pin "P$1_TIP") (pinfunction "TIP_P$1_TIP") (pintype "passive"))
    )
    (net (code "35") (name "Net-(IC5A-Q5)") (class "Default")
      (node (ref "IC5") (pin "3") (pinfunction "Q5_3") (pintype "output"))
      (node (ref "Q5") (pin "P$1_TIP") (pinfunction "TIP_P$1_TIP") (pintype "passive"))
    )
    (net (code "36") (name "Net-(IC5A-Q6)") (class "Default")
      (node (ref "IC5") (pin "2") (pinfunction "Q6_2") (pintype "output"))
      (node (ref "Q6") (pin "P$1_TIP") (pinfunction "TIP_P$1_TIP") (pintype "passive"))
    )
    (net (code "37") (name "Net-(LED1-PadA)") (class "Default")
      (node (ref "LED1") (pin "A") (pinfunction "A_A") (pintype "passive"))
      (node (ref "R1") (pin "2") (pinfunction "2_2") (pintype "passive"))
    )
    (net (code "38") (name "Net-(LED2-PadA)") (class "Default")
      (node (ref "LED2") (pin "A") (pinfunction "A_A") (pintype "passive"))
      (node (ref "R2") (pin "2") (pinfunction "2_2") (pintype "passive"))
    )
    (net (code "39") (name "Net-(LED3-PadA)") (class "Default")
      (node (ref "LED3") (pin "A") (pinfunction "A_A") (pintype "passive"))
      (node (ref "R3") (pin "2") (pinfunction "2_2") (pintype "passive"))
    )
    (net (code "40") (name "Net-(LED4-PadA)") (class "Default")
      (node (ref "LED4") (pin "A") (pinfunction "A_A") (pintype "passive"))
      (node (ref "R4") (pin "2") (pinfunction "2_2") (pintype "passive"))
    )
    (net (code "41") (name "Net-(LED5-PadA)") (class "Default")
      (node (ref "LED5") (pin "A") (pinfunction "A_A") (pintype "passive"))
      (node (ref "R5") (pin "2") (pinfunction "2_2") (pintype "passive"))
    )
    (net (code "42") (name "Net-(LED6-PadA)") (class "Default")
      (node (ref "LED6") (pin "A") (pinfunction "A_A") (pintype "passive"))
      (node (ref "R6") (pin "2") (pinfunction "2_2") (pintype "passive"))
    )
    (net (code "43") (name "Net-(LED7-PadA)") (class "Default")
      (node (ref "LED7") (pin "A") (pinfunction "A_A") (pintype "passive"))
      (node (ref "R7") (pin "2") (pinfunction "2_2") (pintype "passive"))
    )
    (net (code "44") (name "Net-(LED8-PadA)") (class "Default")
      (node (ref "LED8") (pin "A") (pinfunction "A_A") (pintype "passive"))
      (node (ref "R8") (pin "2") (pinfunction "2_2") (pintype "passive"))
    )
    (net (code "45") (name "Net-(LED9-PadA)") (class "Default")
      (node (ref "LED9") (pin "A") (pinfunction "A_A") (pintype "passive"))
      (node (ref "R9") (pin "1") (pinfunction "1_1") (pintype "passive"))
    )
    (net (code "46") (name "Net-(LED10-PadA)") (class "Default")
      (node (ref "LED10") (pin "A") (pinfunction "A_A") (pintype "passive"))
      (node (ref "R10") (pin "1") (pinfunction "1_1") (pintype "passive"))
    )
    (net (code "47") (name "Net-(LED11-PadA)") (class "Default")
      (node (ref "LED11") (pin "A") (pinfunction "A_A") (pintype "passive"))
      (node (ref "R11") (pin "1") (pinfunction "1_1") (pintype "passive"))
    )
    (net (code "48") (name "Net-(LED12-PadA)") (class "Default")
      (node (ref "LED12") (pin "A") (pinfunction "A_A") (pintype "passive"))
      (node (ref "R12") (pin "1") (pinfunction "1_1") (pintype "passive"))
    )
    (net (code "49") (name "Net-(LED13-PadA)") (class "Default")
      (node (ref "LED13") (pin "A") (pinfunction "A_A") (pintype "passive"))
      (node (ref "R13") (pin "1") (pinfunction "1_1") (pintype "passive"))
    )
    (net (code "50") (name "Net-(LED14-PadA)") (class "Default")
      (node (ref "LED14") (pin "A") (pinfunction "A_A") (pintype "passive"))
      (node (ref "R14") (pin "1") (pinfunction "1_1") (pintype "passive"))
    )
    (net (code "51") (name "V+") (class "Default")
      (node (ref "C1") (pin "1") (pinfunction "+_1") (pintype "passive"))
      (node (ref "C3") (pin "1") (pinfunction "1_1") (pintype "passive"))
      (node (ref "IC1") (pin "1") (pinfunction "VI_1") (pintype "input"))
      (node (ref "IC4") (pin "13") (pinfunction "V+_13") (pintype "power_in"))
      (node (ref "U$1") (pin "V+DOTCOM") (pinfunction "V+_V+DOTCOM") (pintype "bidirectional"))
      (node (ref "U$1") (pin "V+EURO1") (pinfunction "V+_V+EURO1") (pintype "bidirectional"))
      (node (ref "U$1") (pin "V+EURO2") (pinfunction "V+_V+EURO2") (pintype "bidirectional"))
      (node (ref "U$1") (pin "V+MOTM") (pinfunction "V+_V+MOTM") (pintype "bidirectional"))
    )
    (net (code "52") (name "V-") (class "Default")
      (node (ref "C2") (pin "2") (pinfunction "-_2") (pintype "passive"))
      (node (ref "IC4") (pin "3") (pinfunction "V-_3") (pintype "power_in"))
      (node (ref "U$1") (pin "V-DOTCOM") (pinfunction "V-_V-DOTCOM") (pintype "bidirectional"))
      (node (ref "U$1") (pin "V-EURO1") (pinfunction "V-_V-EURO1") (pintype "bidirectional"))
      (node (ref "U$1") (pin "V-EURO2") (pinfunction "V-_V-EURO2") (pintype "bidirectional"))
      (node (ref "U$1") (pin "V-MOTM") (pinfunction "V-_V-MOTM") (pintype "bidirectional"))
    )
    (net (code "53") (name "VCC") (class "Default")
      (node (ref "C4") (pin "1") (pinfunction "1_1") (pintype "passive"))
      (node (ref "C5") (pin "1") (pinfunction "1_1") (pintype "passive"))
      (node (ref "C6") (pin "1") (pinfunction "1_1") (pintype "passive"))
      (node (ref "IC1") (pin "3") (pinfunction "VO_3") (pintype "passive"))
      (node (ref "IC2") (pin "16") (pinfunction "VCC_16") (pintype "power_in"))
      (node (ref "IC2") (pin "3") (pinfunction "X_3") (pintype "bidirectional"))
      (node (ref "IC3") (pin "16") (pinfunction "VCC_16") (pintype "power_in"))
      (node (ref "VR1") (pin "3") (pinfunction "E_3") (pintype "passive"))
      (node (ref "VR2") (pin "3") (pinfunction "E_3") (pintype "passive"))
      (node (ref "VR3") (pin "3") (pinfunction "E_3") (pintype "passive"))
      (node (ref "VR4") (pin "3") (pinfunction "E_3") (pintype "passive"))
      (node (ref "VR5") (pin "3") (pinfunction "E_3") (pintype "passive"))
      (node (ref "VR6") (pin "3") (pinfunction "E_3") (pintype "passive"))
      (node (ref "VR7") (pin "3") (pinfunction "E_3") (pintype "passive"))
      (node (ref "VR8") (pin "3") (pinfunction "E_3") (pintype "passive"))
    )
    (net (code "54") (name "unconnected-(A-SWITCH-PadP$2_SWITCH)") (class "Default")
      (node (ref "A") (pin "P$2_SWITCH") (pinfunction "SWITCH_P$2_SWITCH") (pintype "passive"))
    )
    (net (code "55") (name "unconnected-(B-SWITCH-PadP$2_SWITCH)") (class "Default")
      (node (ref "B") (pin "P$2_SWITCH") (pinfunction "SWITCH_P$2_SWITCH") (pintype "passive"))
    )
    (net (code "56") (name "unconnected-(C-SWITCH-PadP$2_SWITCH)") (class "Default")
      (node (ref "C") (pin "P$2_SWITCH") (pinfunction "SWITCH_P$2_SWITCH") (pintype "passive"))
    )
    (net (code "57") (name "unconnected-(CCO1_OUT-SLEEVE-PadP$3_SLEEVE)") (class "Default")
      (node (ref "CCO1_OUT") (pin "P$3_SLEEVE") (pinfunction "SLEEVE_P$3_SLEEVE") (pintype "passive"))
    )
    (net (code "58") (name "unconnected-(CCO1_OUT-SWITCH-PadP$2_SWITCH)") (class "Default")
      (node (ref "CCO1_OUT") (pin "P$2_SWITCH") (pinfunction "SWITCH_P$2_SWITCH") (pintype "passive"))
    )
    (net (code "59") (name "unconnected-(CCO1_OUT-TIP-PadP$1_TIP)") (class "Default")
      (node (ref "CCO1_OUT") (pin "P$1_TIP") (pinfunction "TIP_P$1_TIP") (pintype "passive"))
    )
    (net (code "60") (name "unconnected-(CCO2_OUT-SLEEVE-PadP$3_SLEEVE)") (class "Default")
      (node (ref "CCO2_OUT") (pin "P$3_SLEEVE") (pinfunction "SLEEVE_P$3_SLEEVE") (pintype "passive"))
    )
    (net (code "61") (name "unconnected-(CCO2_OUT-SWITCH-PadP$2_SWITCH)") (class "Default")
      (node (ref "CCO2_OUT") (pin "P$2_SWITCH") (pinfunction "SWITCH_P$2_SWITCH") (pintype "passive"))
    )
    (net (code "62") (name "unconnected-(CCO2_OUT-TIP-PadP$1_TIP)") (class "Default")
      (node (ref "CCO2_OUT") (pin "P$1_TIP") (pinfunction "TIP_P$1_TIP") (pintype "passive"))
    )
    (net (code "63") (name "unconnected-(CCO3_OUT-SLEEVE-PadP$3_SLEEVE)") (class "Default")
      (node (ref "CCO3_OUT") (pin "P$3_SLEEVE") (pinfunction "SLEEVE_P$3_SLEEVE") (pintype "passive"))
    )
    (net (code "64") (name "unconnected-(CCO3_OUT-SWITCH-PadP$2_SWITCH)") (class "Default")
      (node (ref "CCO3_OUT") (pin "P$2_SWITCH") (pinfunction "SWITCH_P$2_SWITCH") (pintype "passive"))
    )
    (net (code "65") (name "unconnected-(CCO3_OUT-TIP-PadP$1_TIP)") (class "Default")
      (node (ref "CCO3_OUT") (pin "P$1_TIP") (pinfunction "TIP_P$1_TIP") (pintype "passive"))
    )
    (net (code "66") (name "unconnected-(CCO4_OUT-SLEEVE-PadP$3_SLEEVE)") (class "Default")
      (node (ref "CCO4_OUT") (pin "P$3_SLEEVE") (pinfunction "SLEEVE_P$3_SLEEVE") (pintype "passive"))
    )
    (net (code "67") (name "unconnected-(CCO4_OUT-SWITCH-PadP$2_SWITCH)") (class "Default")
      (node (ref "CCO4_OUT") (pin "P$2_SWITCH") (pinfunction "SWITCH_P$2_SWITCH") (pintype "passive"))
    )
    (net (code "68") (name "unconnected-(CCO4_OUT-TIP-PadP$1_TIP)") (class "Default")
      (node (ref "CCO4_OUT") (pin "P$1_TIP") (pinfunction "TIP_P$1_TIP") (pintype "passive"))
    )
    (net (code "69") (name "unconnected-(COMPLEX_OUT1-SLEEVE-PadP$3_SLEEVE)") (class "Default")
      (node (ref "COMPLEX_OUT1") (pin "P$3_SLEEVE") (pinfunction "SLEEVE_P$3_SLEEVE") (pintype "passive"))
    )
    (net (code "70") (name "unconnected-(COMPLEX_OUT1-SWITCH-PadP$2_SWITCH)") (class "Default")
      (node (ref "COMPLEX_OUT1") (pin "P$2_SWITCH") (pinfunction "SWITCH_P$2_SWITCH") (pintype "passive"))
    )
    (net (code "71") (name "unconnected-(COMPLEX_OUT1-TIP-PadP$1_TIP)") (class "Default")
      (node (ref "COMPLEX_OUT1") (pin "P$1_TIP") (pinfunction "TIP_P$1_TIP") (pintype "passive"))
    )
    (net (code "72") (name "unconnected-(COMPLEX_OUT2-SLEEVE-PadP$3_SLEEVE)") (class "Default")
      (node (ref "COMPLEX_OUT2") (pin "P$3_SLEEVE") (pinfunction "SLEEVE_P$3_SLEEVE") (pintype "passive"))
    )
    (net (code "73") (name "unconnected-(COMPLEX_OUT2-SWITCH-PadP$2_SWITCH)") (class "Default")
      (node (ref "COMPLEX_OUT2") (pin "P$2_SWITCH") (pinfunction "SWITCH_P$2_SWITCH") (pintype "passive"))
    )
    (net (code "74") (name "unconnected-(COMPLEX_OUT2-TIP-PadP$1_TIP)") (class "Default")
      (node (ref "COMPLEX_OUT2") (pin "P$1_TIP") (pinfunction "TIP_P$1_TIP") (pintype "passive"))
    )
    (net (code "75") (name "unconnected-(IC4-EN-Pad2)") (class "Default")
      (node (ref "IC4") (pin "2") (pinfunction "EN_2") (pintype "input"))
    )
    (net (code "76") (name "unconnected-(IC5A-P1-Pad10)") (class "Default")
      (node (ref "IC5") (pin "10") (pinfunction "P1_10") (pintype "input"))
    )
    (net (code "77") (name "unconnected-(IC5A-Q7-Pad4)") (class "Default")
      (node (ref "IC5") (pin "4") (pinfunction "Q7_4") (pintype "output"))
    )
    (net (code "78") (name "unconnected-(IC5A-Q8-Pad13)") (class "Default")
      (node (ref "IC5") (pin "13") (pinfunction "Q8_13") (pintype "output"))
    )
    (net (code "79") (name "unconnected-(IC5A-Q9-Pad12)") (class "Default")
      (node (ref "IC5") (pin "12") (pinfunction "Q9_12") (pintype "output"))
    )
    (net (code "80") (name "unconnected-(IC5A-Q10-Pad14)") (class "Default")
      (node (ref "IC5") (pin "14") (pinfunction "Q10_14") (pintype "output"))
    )
    (net (code "81") (name "unconnected-(IC5A-Q11-Pad15)") (class "Default")
      (node (ref "IC5") (pin "15") (pinfunction "Q11_15") (pintype "output"))
    )
    (net (code "82") (name "unconnected-(IC5A-Q12-Pad1)") (class "Default")
      (node (ref "IC5") (pin "1") (pinfunction "Q12_1") (pintype "output"))
    )
    (net (code "83") (name "unconnected-(IC5A-RES-Pad11)") (class "Default")
      (node (ref "IC5") (pin "11") (pinfunction "RES_11") (pintype "input"))
    )
    (net (code "84") (name "unconnected-(IC6A-I-Pad1)") (class "Default")
      (node (ref "IC6") (pin "1") (pinfunction "I_1") (pintype "input"))
    )
    (net (code "85") (name "unconnected-(IC6A-O-Pad2)") (class "Default")
      (node (ref "IC6") (pin "2") (pinfunction "O_2") (pintype "output"))
    )
    (net (code "86") (name "unconnected-(IC6B-I-Pad3)") (class "Default")
      (node (ref "IC6") (pin "3") (pinfunction "I_3") (pintype "input"))
    )
    (net (code "87") (name "unconnected-(IC6B-O-Pad4)") (class "Default")
      (node (ref "IC6") (pin "4") (pinfunction "O_4") (pintype "output"))
    )
    (net (code "88") (name "unconnected-(IC6C-I-Pad5)") (class "Default")
      (node (ref "IC6") (pin "5") (pinfunction "I_5") (pintype "input"))
    )
    (net (code "89") (name "unconnected-(IC6C-O-Pad6)") (class "Default")
      (node (ref "IC6") (pin "6") (pinfunction "O_6") (pintype "output"))
    )
    (net (code "90") (name "unconnected-(IC6D-I-Pad9)") (class "Default")
      (node (ref "IC6") (pin "9") (pinfunction "I_9") (pintype "input"))
    )
    (net (code "91") (name "unconnected-(IC6D-O-Pad8)") (class "Default")
      (node (ref "IC6") (pin "8") (pinfunction "O_8") (pintype "output"))
    )
    (net (code "92") (name "unconnected-(IC6E-I-Pad11)") (class "Default")
      (node (ref "IC6") (pin "11") (pinfunction "I_11") (pintype "input"))
    )
    (net (code "93") (name "unconnected-(IC6E-O-Pad10)") (class "Default")
      (node (ref "IC6") (pin "10") (pinfunction "O_10") (pintype "output"))
    )
    (net (code "94") (name "unconnected-(IC6F-I-Pad13)") (class "Default")
      (node (ref "IC6") (pin "13") (pinfunction "I_13") (pintype "input"))
    )
    (net (code "95") (name "unconnected-(IC6F-O-Pad12)") (class "Default")
      (node (ref "IC6") (pin "12") (pinfunction "O_12") (pintype "output"))
    )
    (net (code "96") (name "unconnected-(IC7A-I0-Pad1)") (class "Default")
      (node (ref "IC7") (pin "1") (pinfunction "I0_1") (pintype "input"))
    )
    (net (code "97") (name "unconnected-(IC7A-I1-Pad2)") (class "Default")
      (node (ref "IC7") (pin "2") (pinfunction "I1_2") (pintype "input"))
    )
    (net (code "98") (name "unconnected-(IC7A-O-Pad3)") (class "Default")
      (node (ref "IC7") (pin "3") (pinfunction "O_3") (pintype "output"))
    )
    (net (code "99") (name "unconnected-(IC7B-I0-Pad5)") (class "Default")
      (node (ref "IC7") (pin "5") (pinfunction "I0_5") (pintype "input"))
    )
    (net (code "100") (name "unconnected-(IC7B-I1-Pad6)") (class "Default")
      (node (ref "IC7") (pin "6") (pinfunction "I1_6") (pintype "input"))
    )
    (net (code "101") (name "unconnected-(IC7B-O-Pad4)") (class "Default")
      (node (ref "IC7") (pin "4") (pinfunction "O_4") (pintype "output"))
    )
    (net (code "102") (name "unconnected-(IC7C-I0-Pad8)") (class "Default")
      (node (ref "IC7") (pin "8") (pinfunction "I0_8") (pintype "input"))
    )
    (net (code "103") (name "unconnected-(IC7C-I1-Pad9)") (class "Default")
      (node (ref "IC7") (pin "9") (pinfunction "I1_9") (pintype "input"))
    )
    (net (code "104") (name "unconnected-(IC7C-O-Pad10)") (class "Default")
      (node (ref "IC7") (pin "10") (pinfunction "O_10") (pintype "output"))
    )
    (net (code "105") (name "unconnected-(IC7D-I0-Pad12)") (class "Default")
      (node (ref "IC7") (pin "12") (pinfunction "I0_12") (pintype "input"))
    )
    (net (code "106") (name "unconnected-(IC7D-I1-Pad13)") (class "Default")
      (node (ref "IC7") (pin "13") (pinfunction "I1_13") (pintype "input"))
    )
    (net (code "107") (name "unconnected-(IC7D-O-Pad11)") (class "Default")
      (node (ref "IC7") (pin "11") (pinfunction "O_11") (pintype "output"))
    )
    (net (code "108") (name "unconnected-(MUX1-SWITCH-PadP$2_SWITCH)") (class "Default")
      (node (ref "MUX1") (pin "P$2_SWITCH") (pinfunction "SWITCH_P$2_SWITCH") (pintype "passive"))
    )
    (net (code "109") (name "unconnected-(MUX2-SWITCH-PadP$2_SWITCH)") (class "Default")
      (node (ref "MUX2") (pin "P$2_SWITCH") (pinfunction "SWITCH_P$2_SWITCH") (pintype "passive"))
    )
    (net (code "110") (name "unconnected-(MUX3-SWITCH-PadP$2_SWITCH)") (class "Default")
      (node (ref "MUX3") (pin "P$2_SWITCH") (pinfunction "SWITCH_P$2_SWITCH") (pintype "passive"))
    )
    (net (code "111") (name "unconnected-(MUX4-SWITCH-PadP$2_SWITCH)") (class "Default")
      (node (ref "MUX4") (pin "P$2_SWITCH") (pinfunction "SWITCH_P$2_SWITCH") (pintype "passive"))
    )
    (net (code "112") (name "unconnected-(MUX5-SWITCH-PadP$2_SWITCH)") (class "Default")
      (node (ref "MUX5") (pin "P$2_SWITCH") (pinfunction "SWITCH_P$2_SWITCH") (pintype "passive"))
    )
    (net (code "113") (name "unconnected-(MUX6-SWITCH-PadP$2_SWITCH)") (class "Default")
      (node (ref "MUX6") (pin "P$2_SWITCH") (pinfunction "SWITCH_P$2_SWITCH") (pintype "passive"))
    )
    (net (code "114") (name "unconnected-(MUX7-SWITCH-PadP$2_SWITCH)") (class "Default")
      (node (ref "MUX7") (pin "P$2_SWITCH") (pinfunction "SWITCH_P$2_SWITCH") (pintype "passive"))
    )
    (net (code "115") (name "unconnected-(MUX8-SWITCH-PadP$2_SWITCH)") (class "Default")
      (node (ref "MUX8") (pin "P$2_SWITCH") (pinfunction "SWITCH_P$2_SWITCH") (pintype "passive"))
    )
    (net (code "116") (name "unconnected-(MUX_OUT-SWITCH-PadP$2_SWITCH)") (class "Default")
      (node (ref "MUX_OUT") (pin "P$2_SWITCH") (pinfunction "SWITCH_P$2_SWITCH") (pintype "passive"))
    )
    (net (code "117") (name "unconnected-(Q1-SWITCH-PadP$2_SWITCH)") (class "Default")
      (node (ref "Q1") (pin "P$2_SWITCH") (pinfunction "SWITCH_P$2_SWITCH") (pintype "passive"))
    )
    (net (code "118") (name "unconnected-(Q2-SWITCH-PadP$2_SWITCH)") (class "Default")
      (node (ref "Q2") (pin "P$2_SWITCH") (pinfunction "SWITCH_P$2_SWITCH") (pintype "passive"))
    )
    (net (code "119") (name "unconnected-(Q3-SWITCH-PadP$2_SWITCH)") (class "Default")
      (node (ref "Q3") (pin "P$2_SWITCH") (pinfunction "SWITCH_P$2_SWITCH") (pintype "passive"))
    )
    (net (code "120") (name "unconnected-(Q4-SWITCH-PadP$2_SWITCH)") (class "Default")
      (node (ref "Q4") (pin "P$2_SWITCH") (pinfunction "SWITCH_P$2_SWITCH") (pintype "passive"))
    )
    (net (code "121") (name "unconnected-(Q5-SWITCH-PadP$2_SWITCH)") (class "Default")
      (node (ref "Q5") (pin "P$2_SWITCH") (pinfunction "SWITCH_P$2_SWITCH") (pintype "passive"))
    )
    (net (code "122") (name "unconnected-(Q6-SWITCH-PadP$2_SWITCH)") (class "Default")
      (node (ref "Q6") (pin "P$2_SWITCH") (pinfunction "SWITCH_P$2_SWITCH") (pintype "passive"))
    )
    (net (code "123") (name "unconnected-(R11-Pad2)") (class "Default")
      (node (ref "R11") (pin "2") (pinfunction "2_2") (pintype "passive"))
    )
    (net (code "124") (name "unconnected-(R12-Pad2)") (class "Default")
      (node (ref "R12") (pin "2") (pinfunction "2_2") (pintype "passive"))
    )
    (net (code "125") (name "unconnected-(R13-Pad2)") (class "Default")
      (node (ref "R13") (pin "2") (pinfunction "2_2") (pintype "passive"))
    )
    (net (code "126") (name "unconnected-(R14-Pad2)") (class "Default")
      (node (ref "R14") (pin "2") (pinfunction "2_2") (pintype "passive"))
    )
    (net (code "127") (name "unconnected-(U1A-+IN-Pad3)") (class "Default")
      (node (ref "U1") (pin "3") (pinfunction "+IN_3") (pintype "input"))
    )
    (net (code "128") (name "unconnected-(U1A--IN-Pad2)") (class "Default")
      (node (ref "U1") (pin "2") (pinfunction "-IN_2") (pintype "input"))
    )
    (net (code "129") (name "unconnected-(U1A-OUT-Pad1)") (class "Default")
      (node (ref "U1") (pin "1") (pinfunction "OUT_1") (pintype "output"))
    )
    (net (code "130") (name "unconnected-(U1B-+IN-Pad5)") (class "Default")
      (node (ref "U1") (pin "5") (pinfunction "+IN_5") (pintype "input"))
    )
    (net (code "131") (name "unconnected-(U1B--IN-Pad6)") (class "Default")
      (node (ref "U1") (pin "6") (pinfunction "-IN_6") (pintype "input"))
    )
    (net (code "132") (name "unconnected-(U1B-OUT-Pad7)") (class "Default")
      (node (ref "U1") (pin "7") (pinfunction "OUT_7") (pintype "output"))
    )
    (net (code "133") (name "unconnected-(U1C-+IN-Pad10)") (class "Default")
      (node (ref "U1") (pin "10") (pinfunction "+IN_10") (pintype "input"))
    )
    (net (code "134") (name "unconnected-(U1C--IN-Pad9)") (class "Default")
      (node (ref "U1") (pin "9") (pinfunction "-IN_9") (pintype "input"))
    )
    (net (code "135") (name "unconnected-(U1C-OUT-Pad8)") (class "Default")
      (node (ref "U1") (pin "8") (pinfunction "OUT_8") (pintype "output"))
    )
    (net (code "136") (name "unconnected-(U1D-+IN-Pad12)") (class "Default")
      (node (ref "U1") (pin "12") (pinfunction "+IN_12") (pintype "input"))
    )
    (net (code "137") (name "unconnected-(U1D--IN-Pad13)") (class "Default")
      (node (ref "U1") (pin "13") (pinfunction "-IN_13") (pintype "input"))
    )
    (net (code "138") (name "unconnected-(U1D-OUT-Pad14)") (class "Default")
      (node (ref "U1") (pin "14") (pinfunction "OUT_14") (pintype "output"))
    )
    (net (code "139") (name "unconnected-(U2A-+IN-Pad3)") (class "Default")
      (node (ref "U2") (pin "3") (pinfunction "+IN_3") (pintype "input"))
    )
    (net (code "140") (name "unconnected-(U2A--IN-Pad2)") (class "Default")
      (node (ref "U2") (pin "2") (pinfunction "-IN_2") (pintype "input"))
    )
    (net (code "141") (name "unconnected-(U2A-OUT-Pad1)") (class "Default")
      (node (ref "U2") (pin "1") (pinfunction "OUT_1") (pintype "output"))
    )
    (net (code "142") (name "unconnected-(U2B-+IN-Pad5)") (class "Default")
      (node (ref "U2") (pin "5") (pinfunction "+IN_5") (pintype "input"))
    )
    (net (code "143") (name "unconnected-(U2B--IN-Pad6)") (class "Default")
      (node (ref "U2") (pin "6") (pinfunction "-IN_6") (pintype "input"))
    )
    (net (code "144") (name "unconnected-(U2B-OUT-Pad7)") (class "Default")
      (node (ref "U2") (pin "7") (pinfunction "OUT_7") (pintype "output"))
    )
    (net (code "145") (name "unconnected-(U2C-+IN-Pad10)") (class "Default")
      (node (ref "U2") (pin "10") (pinfunction "+IN_10") (pintype "input"))
    )
    (net (code "146") (name "unconnected-(U2C--IN-Pad9)") (class "Default")
      (node (ref "U2") (pin "9") (pinfunction "-IN_9") (pintype "input"))
    )
    (net (code "147") (name "unconnected-(U2C-OUT-Pad8)") (class "Default")
      (node (ref "U2") (pin "8") (pinfunction "OUT_8") (pintype "output"))
    )
    (net (code "148") (name "unconnected-(U2D-+IN-Pad12)") (class "Default")
      (node (ref "U2") (pin "12") (pinfunction "+IN_12") (pintype "input"))
    )
    (net (code "149") (name "unconnected-(U2D--IN-Pad13)") (class "Default")
      (node (ref "U2") (pin "13") (pinfunction "-IN_13") (pintype "input"))
    )
    (net (code "150") (name "unconnected-(U2D-OUT-Pad14)") (class "Default")
      (node (ref "U2") (pin "14") (pinfunction "OUT_14") (pintype "output"))
    )
    (net (code "151") (name "unconnected-(VCO1_OUT-SLEEVE-PadP$3_SLEEVE)") (class "Default")
      (node (ref "VCO1_OUT") (pin "P$3_SLEEVE") (pinfunction "SLEEVE_P$3_SLEEVE") (pintype "passive"))
    )
    (net (code "152") (name "unconnected-(VCO1_OUT-SWITCH-PadP$2_SWITCH)") (class "Default")
      (node (ref "VCO1_OUT") (pin "P$2_SWITCH") (pinfunction "SWITCH_P$2_SWITCH") (pintype "passive"))
    )
    (net (code "153") (name "unconnected-(VCO1_OUT-TIP-PadP$1_TIP)") (class "Default")
      (node (ref "VCO1_OUT") (pin "P$1_TIP") (pinfunction "TIP_P$1_TIP") (pintype "passive"))
    )
    (net (code "154") (name "unconnected-(VCO2_OUT-SLEEVE-PadP$3_SLEEVE)") (class "Default")
      (node (ref "VCO2_OUT") (pin "P$3_SLEEVE") (pinfunction "SLEEVE_P$3_SLEEVE") (pintype "passive"))
    )
    (net (code "155") (name "unconnected-(VCO2_OUT-SWITCH-PadP$2_SWITCH)") (class "Default")
      (node (ref "VCO2_OUT") (pin "P$2_SWITCH") (pinfunction "SWITCH_P$2_SWITCH") (pintype "passive"))
    )
    (net (code "156") (name "unconnected-(VCO2_OUT-TIP-PadP$1_TIP)") (class "Default")
      (node (ref "VCO2_OUT") (pin "P$1_TIP") (pinfunction "TIP_P$1_TIP") (pintype "passive"))
    )
  )
)
